# working.net
KiCad netlist of a schematic drawn in EAGLE
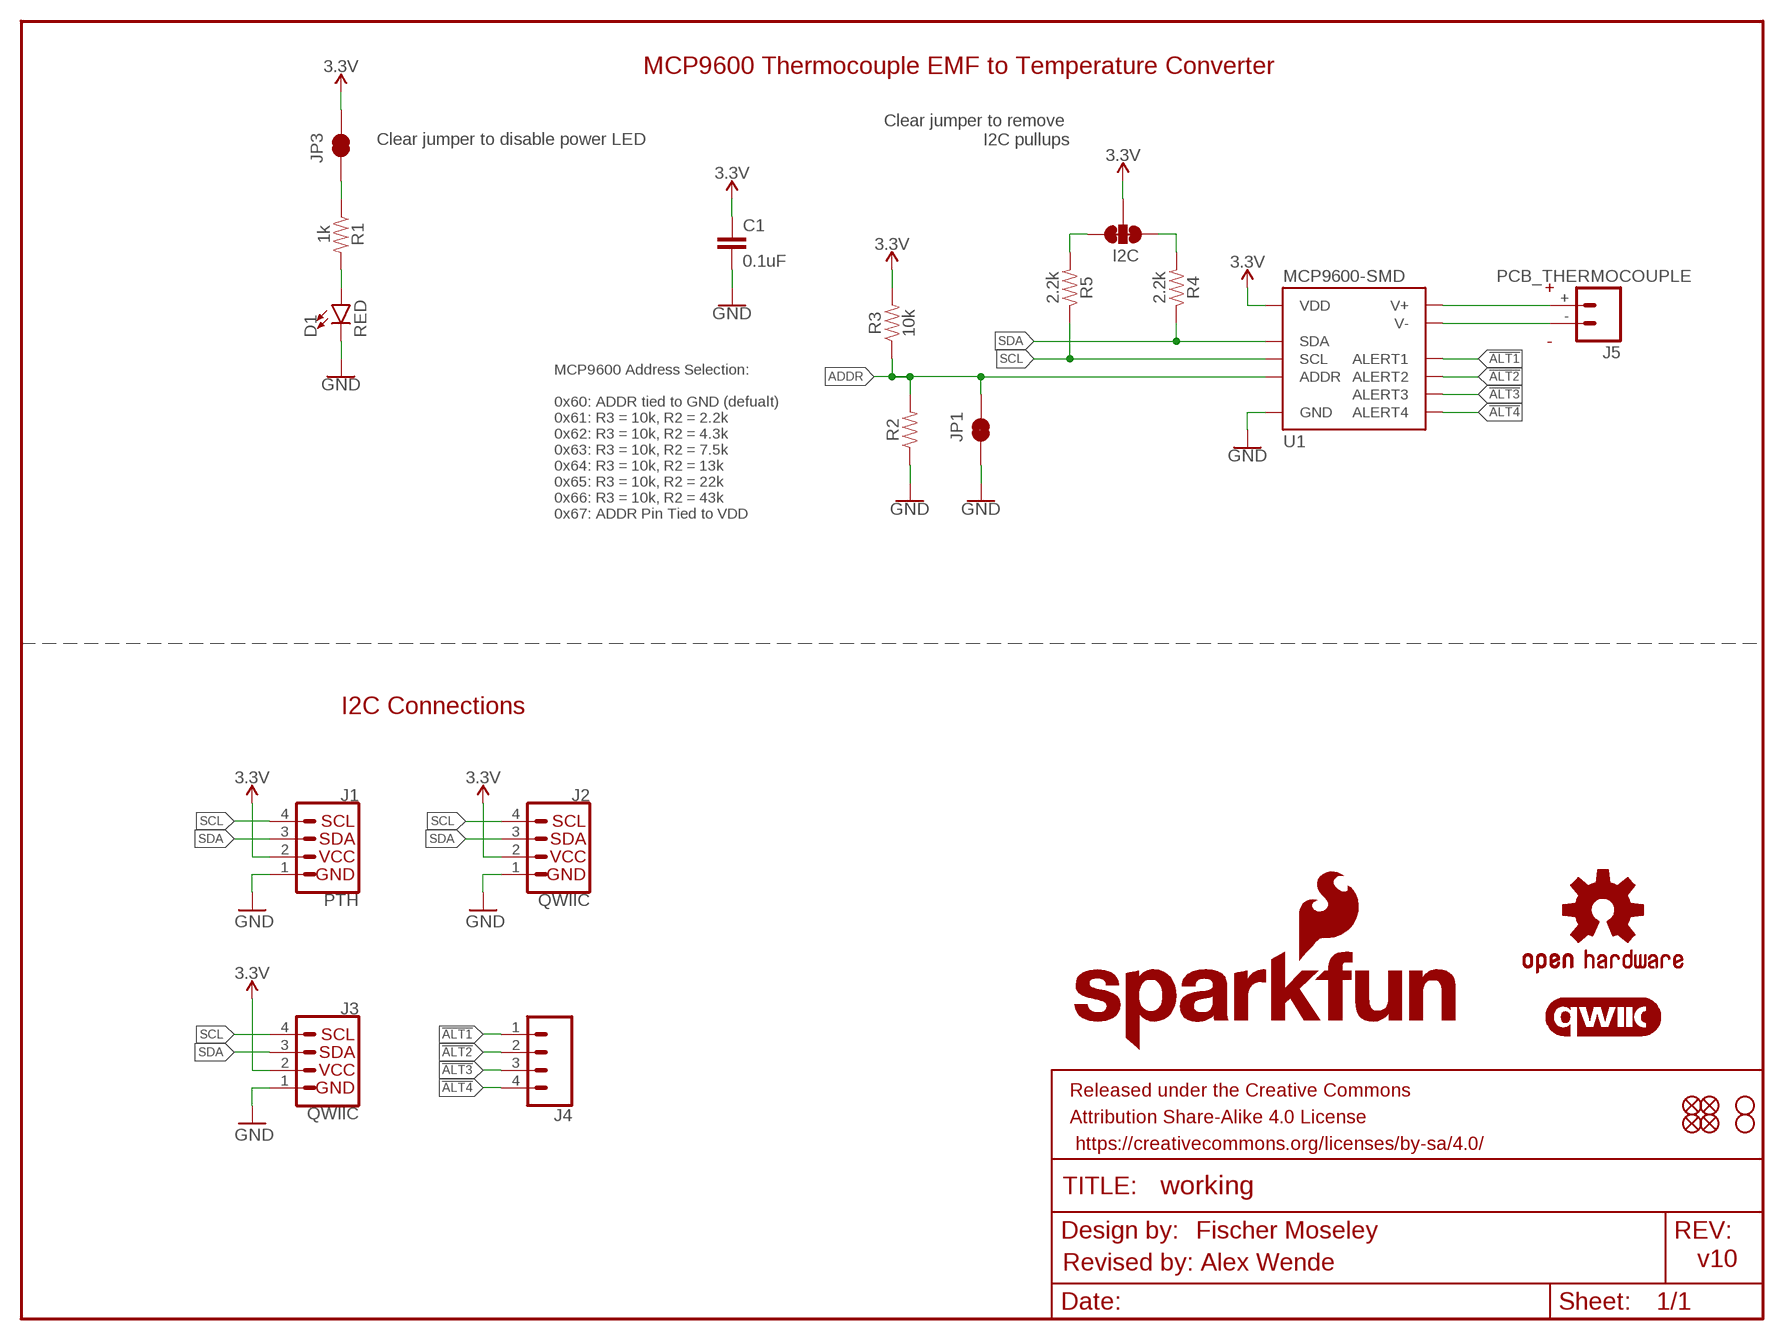
[diagram p0: schematic, sheet 1]

(export (version "E")
  (design (tool "Eeschema 10.0.6"))
  (components
    (comp (ref "C1")
      (value "0.1uF")
      (footprint "eagle-import:0603")
      (libsource (lib "eagle-import") (part "0.1UF-0603-25V-(+80/-20%)"))
    )
    (comp (ref "D1")
      (value "RED")
      (footprint "eagle-import:LED-0603")
      (libsource (lib "eagle-import") (part "LED-RED0603"))
    )
    (comp (ref "FD1")
      (value "FIDUCIALUFIDUCIAL")
      (footprint "eagle-import:FIDUCIAL-MICRO")
      (libsource (lib "eagle-import") (part "FIDUCIALUFIDUCIAL"))
    )
    (comp (ref "FD2")
      (value "FIDUCIALUFIDUCIAL")
      (footprint "eagle-import:FIDUCIAL-MICRO")
      (libsource (lib "eagle-import") (part "FIDUCIALUFIDUCIAL"))
    )
    (comp (ref "FD3")
      (value "FIDUCIALUFIDUCIAL")
      (footprint "eagle-import:FIDUCIAL-MICRO")
      (libsource (lib "eagle-import") (part "FIDUCIALUFIDUCIAL"))
    )
    (comp (ref "FD4")
      (value "FIDUCIALUFIDUCIAL")
      (footprint "eagle-import:FIDUCIAL-MICRO")
      (libsource (lib "eagle-import") (part "FIDUCIALUFIDUCIAL"))
    )
    (comp (ref "FRAME1")
      (value "FRAME-LETTER")
      (footprint "eagle-import:CREATIVE_COMMONS")
      (libsource (lib "eagle-import") (part "FRAME-LETTER"))
    )
    (comp (ref "J1")
      (value "PTH")
      (footprint "eagle-import:1X04_NO_SILK")
      (libsource (lib "eagle-import") (part "I2C_STANDARD_NO_SILK"))
    )
    (comp (ref "J2")
      (value "QWIIC")
      (footprint "eagle-import:JST04_1MM_RA")
      (libsource (lib "eagle-import") (part "QWIIC_CONNECTORJS-1MM"))
    )
    (comp (ref "J3")
      (value "QWIIC")
      (footprint "eagle-import:JST04_1MM_RA")
      (libsource (lib "eagle-import") (part "QWIIC_CONNECTORJS-1MM"))
    )
    (comp (ref "J4")
      (value "CONN_041X04_NO_SILK")
      (footprint "eagle-import:1X04_NO_SILK")
      (libsource (lib "eagle-import") (part "CONN_041X04_NO_SILK"))
    )
    (comp (ref "J5")
      (value "PCB_THERMOCOUPLE")
      (footprint "eagle-import:PCC-SMP")
      (libsource (lib "eagle-import") (part "PCB_THERMOCOUPLE"))
    )
    (comp (ref "JP1")
      (value "JUMPER-SMT_2_NC_TRACE_SILK")
      (footprint "eagle-import:SMT-JUMPER_2_NC_TRACE_SILK")
      (libsource (lib "eagle-import") (part "JUMPER-SMT_2_NC_TRACE_SILK"))
    )
    (comp (ref "JP2")
      (value "I2C")
      (footprint "eagle-import:SMT-JUMPER_3_2-NC_TRACE_SILK")
      (libsource (lib "eagle-import") (part "JUMPER-SMT_3_2-NC_TRACE_SILK"))
    )
    (comp (ref "JP3")
      (value "JUMPER-SMT_2_NC_TRACE_SILK")
      (footprint "eagle-import:SMT-JUMPER_2_NC_TRACE_SILK")
      (libsource (lib "eagle-import") (part "JUMPER-SMT_2_NC_TRACE_SILK"))
    )
    (comp (ref "JP8")
      (value "STAND-OFF")
      (footprint "eagle-import:STAND-OFF")
      (libsource (lib "eagle-import") (part "STAND-OFF"))
    )
    (comp (ref "JP9")
      (value "STAND-OFF")
      (footprint "eagle-import:STAND-OFF")
      (libsource (lib "eagle-import") (part "STAND-OFF"))
    )
    (comp (ref "LOGO1")
      (value "OSHW-LOGOMINI")
      (footprint "eagle-import:OSHW-LOGO-MINI")
      (libsource (lib "eagle-import") (part "OSHW-LOGOMINI"))
    )
    (comp (ref "LOGO2")
      (value "SFE_LOGO_NAME_FLAME.1_INCH")
      (footprint "eagle-import:SFE_LOGO_NAME_FLAME_.1")
      (libsource (lib "eagle-import") (part "SFE_LOGO_NAME_FLAME.1_INCH"))
    )
    (comp (ref "LOGO3")
      (value "QWIIC_LOGO_5MM")
      (footprint "eagle-import:QWIIC_5MM")
      (libsource (lib "eagle-import") (part "QWIIC_LOGO_5MM"))
    )
    (comp (ref "R1")
      (value "1k")
      (footprint "eagle-import:0603")
      (libsource (lib "eagle-import") (part "1KOHM-0603-1/10W-1%"))
    )
    (comp (ref "R2")
      (value "RESISTORAXIAL-0.3-KIT")
      (footprint "eagle-import:AXIAL-0.3-KIT")
      (libsource (lib "eagle-import") (part "RESISTORAXIAL-0.3-KIT"))
    )
    (comp (ref "R3")
      (value "10k")
      (footprint "eagle-import:0603")
      (libsource (lib "eagle-import") (part "10KOHM-0603-1/10W-1%"))
    )
    (comp (ref "R4")
      (value "2.2k")
      (footprint "eagle-import:0603")
      (libsource (lib "eagle-import") (part "2.2KOHM-0603-1/10W-1%"))
    )
    (comp (ref "R5")
      (value "2.2k")
      (footprint "eagle-import:0603")
      (libsource (lib "eagle-import") (part "2.2KOHM-0603-1/10W-1%"))
    )
    (comp (ref "U1")
      (value "MCP9600-SMD")
      (footprint "eagle-import:MQFN-20")
      (libsource (lib "eagle-import") (part "MCP9600-SMD"))
    )
  )
  (nets
    (net (code "1") (name "/~{ALT1}") (class "Default")
      (node (ref "J4") (pin "1") (pinfunction "1_1") (pintype "passive"))
      (node (ref "U1") (pin "11") (pinfunction "ALERT1_11") (pintype "bidirectional"))
    )
    (net (code "2") (name "/~{ALT2}") (class "Default")
      (node (ref "J4") (pin "2") (pinfunction "2_2") (pintype "passive"))
      (node (ref "U1") (pin "12") (pinfunction "ALERT2_12") (pintype "bidirectional"))
    )
    (net (code "3") (name "/~{ALT3}") (class "Default")
      (node (ref "J4") (pin "3") (pinfunction "3_3") (pintype "passive"))
      (node (ref "U1") (pin "14") (pinfunction "ALERT3_14") (pintype "bidirectional"))
    )
    (net (code "4") (name "/~{ALT4}") (class "Default")
      (node (ref "J4") (pin "4") (pinfunction "4_4") (pintype "passive"))
      (node (ref "U1") (pin "15") (pinfunction "ALERT4_15") (pintype "bidirectional"))
    )
    (net (code "5") (name "3.3V") (class "Default")
      (node (ref "C1") (pin "1") (pinfunction "1_1") (pintype "passive"))
      (node (ref "J1") (pin "2") (pinfunction "2_2") (pintype "power_in"))
      (node (ref "J2") (pin "2") (pinfunction "2_2") (pintype "power_in"))
      (node (ref "J3") (pin "2") (pinfunction "2_2") (pintype "power_in"))
      (node (ref "JP2") (pin "2") (pinfunction "2_2") (pintype "passive"))
      (node (ref "JP3") (pin "2") (pinfunction "2_2") (pintype "passive"))
      (node (ref "R3") (pin "2") (pinfunction "2_2") (pintype "passive"))
      (node (ref "U1") (pin "8") (pinfunction "VDD_8") (pintype "bidirectional"))
    )
    (net (code "6") (name "ADDR") (class "Default")
      (node (ref "JP1") (pin "1") (pinfunction "1_1") (pintype "passive"))
      (node (ref "R2") (pin "P$2") (pinfunction "2_P$2") (pintype "passive"))
      (node (ref "R3") (pin "1") (pinfunction "1_1") (pintype "passive"))
      (node (ref "U1") (pin "16") (pinfunction "ADDR_16") (pintype "bidirectional"))
    )
    (net (code "7") (name "GND") (class "Default")
      (node (ref "C1") (pin "2") (pinfunction "2_2") (pintype "passive"))
      (node (ref "D1") (pin "C") (pinfunction "C_C") (pintype "passive"))
      (node (ref "J1") (pin "1") (pinfunction "1_1") (pintype "power_in"))
      (node (ref "J2") (pin "1") (pinfunction "1_1") (pintype "power_in"))
      (node (ref "J3") (pin "1") (pinfunction "1_1") (pintype "power_in"))
      (node (ref "JP1") (pin "2") (pinfunction "2_2") (pintype "passive"))
      (node (ref "R2") (pin "P$1") (pinfunction "1_P$1") (pintype "passive"))
      (node (ref "U1") (pin "1") (pinfunction "GND_1") (pintype "bidirectional"))
      (node (ref "U1") (pin "10") (pinfunction "GND_10") (pintype "bidirectional"))
      (node (ref "U1") (pin "13") (pinfunction "GND_13") (pintype "bidirectional"))
      (node (ref "U1") (pin "17") (pinfunction "GND_17") (pintype "bidirectional"))
      (node (ref "U1") (pin "18") (pinfunction "GND_18") (pintype "bidirectional"))
      (node (ref "U1") (pin "21") (pinfunction "GND_21") (pintype "bidirectional"))
      (node (ref "U1") (pin "3") (pinfunction "GND_3") (pintype "bidirectional"))
      (node (ref "U1") (pin "5") (pinfunction "GND_5") (pintype "bidirectional"))
      (node (ref "U1") (pin "6") (pinfunction "GND_6") (pintype "bidirectional"))
      (node (ref "U1") (pin "7") (pinfunction "GND_7") (pintype "bidirectional"))
      (node (ref "U1") (pin "9") (pinfunction "GND_9") (pintype "bidirectional"))
    )
    (net (code "8") (name "Net-(D1-PadA)") (class "Default")
      (node (ref "D1") (pin "A") (pinfunction "A_A") (pintype "passive"))
      (node (ref "R1") (pin "2") (pinfunction "2_2") (pintype "passive"))
    )
    (net (code "9") (name "Net-(JP2-Pad1)") (class "Default")
      (node (ref "JP2") (pin "1") (pinfunction "1_1") (pintype "passive"))
      (node (ref "R5") (pin "2") (pinfunction "2_2") (pintype "passive"))
    )
    (net (code "10") (name "Net-(JP2-Pad3)") (class "Default")
      (node (ref "JP2") (pin "3") (pinfunction "3_3") (pintype "passive"))
      (node (ref "R4") (pin "2") (pinfunction "2_2") (pintype "passive"))
    )
    (net (code "11") (name "Net-(JP3-Pad1)") (class "Default")
      (node (ref "JP3") (pin "1") (pinfunction "1_1") (pintype "passive"))
      (node (ref "R1") (pin "1") (pinfunction "1_1") (pintype "passive"))
    )
    (net (code "12") (name "Net-(U1-V+)") (class "Default")
      (node (ref "J5") (pin "+") (pinfunction "+_+") (pintype "passive"))
      (node (ref "U1") (pin "2") (pinfunction "V+_2") (pintype "bidirectional"))
    )
    (net (code "13") (name "Net-(U1-V-)") (class "Default")
      (node (ref "J5") (pin "-") (pinfunction "-_-") (pintype "passive"))
      (node (ref "U1") (pin "4") (pinfunction "V-_4") (pintype "bidirectional"))
    )
    (net (code "14") (name "SCL") (class "Default")
      (node (ref "J1") (pin "4") (pinfunction "4_4") (pintype "passive"))
      (node (ref "J2") (pin "4") (pinfunction "4_4") (pintype "passive"))
      (node (ref "J3") (pin "4") (pinfunction "4_4") (pintype "passive"))
      (node (ref "R5") (pin "1") (pinfunction "1_1") (pintype "passive"))
      (node (ref "U1") (pin "19") (pinfunction "SCL_19") (pintype "bidirectional"))
    )
    (net (code "15") (name "SDA") (class "Default")
      (node (ref "J1") (pin "3") (pinfunction "3_3") (pintype "passive"))
      (node (ref "J2") (pin "3") (pinfunction "3_3") (pintype "passive"))
      (node (ref "J3") (pin "3") (pinfunction "3_3") (pintype "passive"))
      (node (ref "R4") (pin "1") (pinfunction "1_1") (pintype "passive"))
      (node (ref "U1") (pin "20") (pinfunction "SDA_20") (pintype "bidirectional"))
    )
  )
)
